# Fall2018AvionicsBay.net
KiCad netlist of a schematic drawn in EAGLE
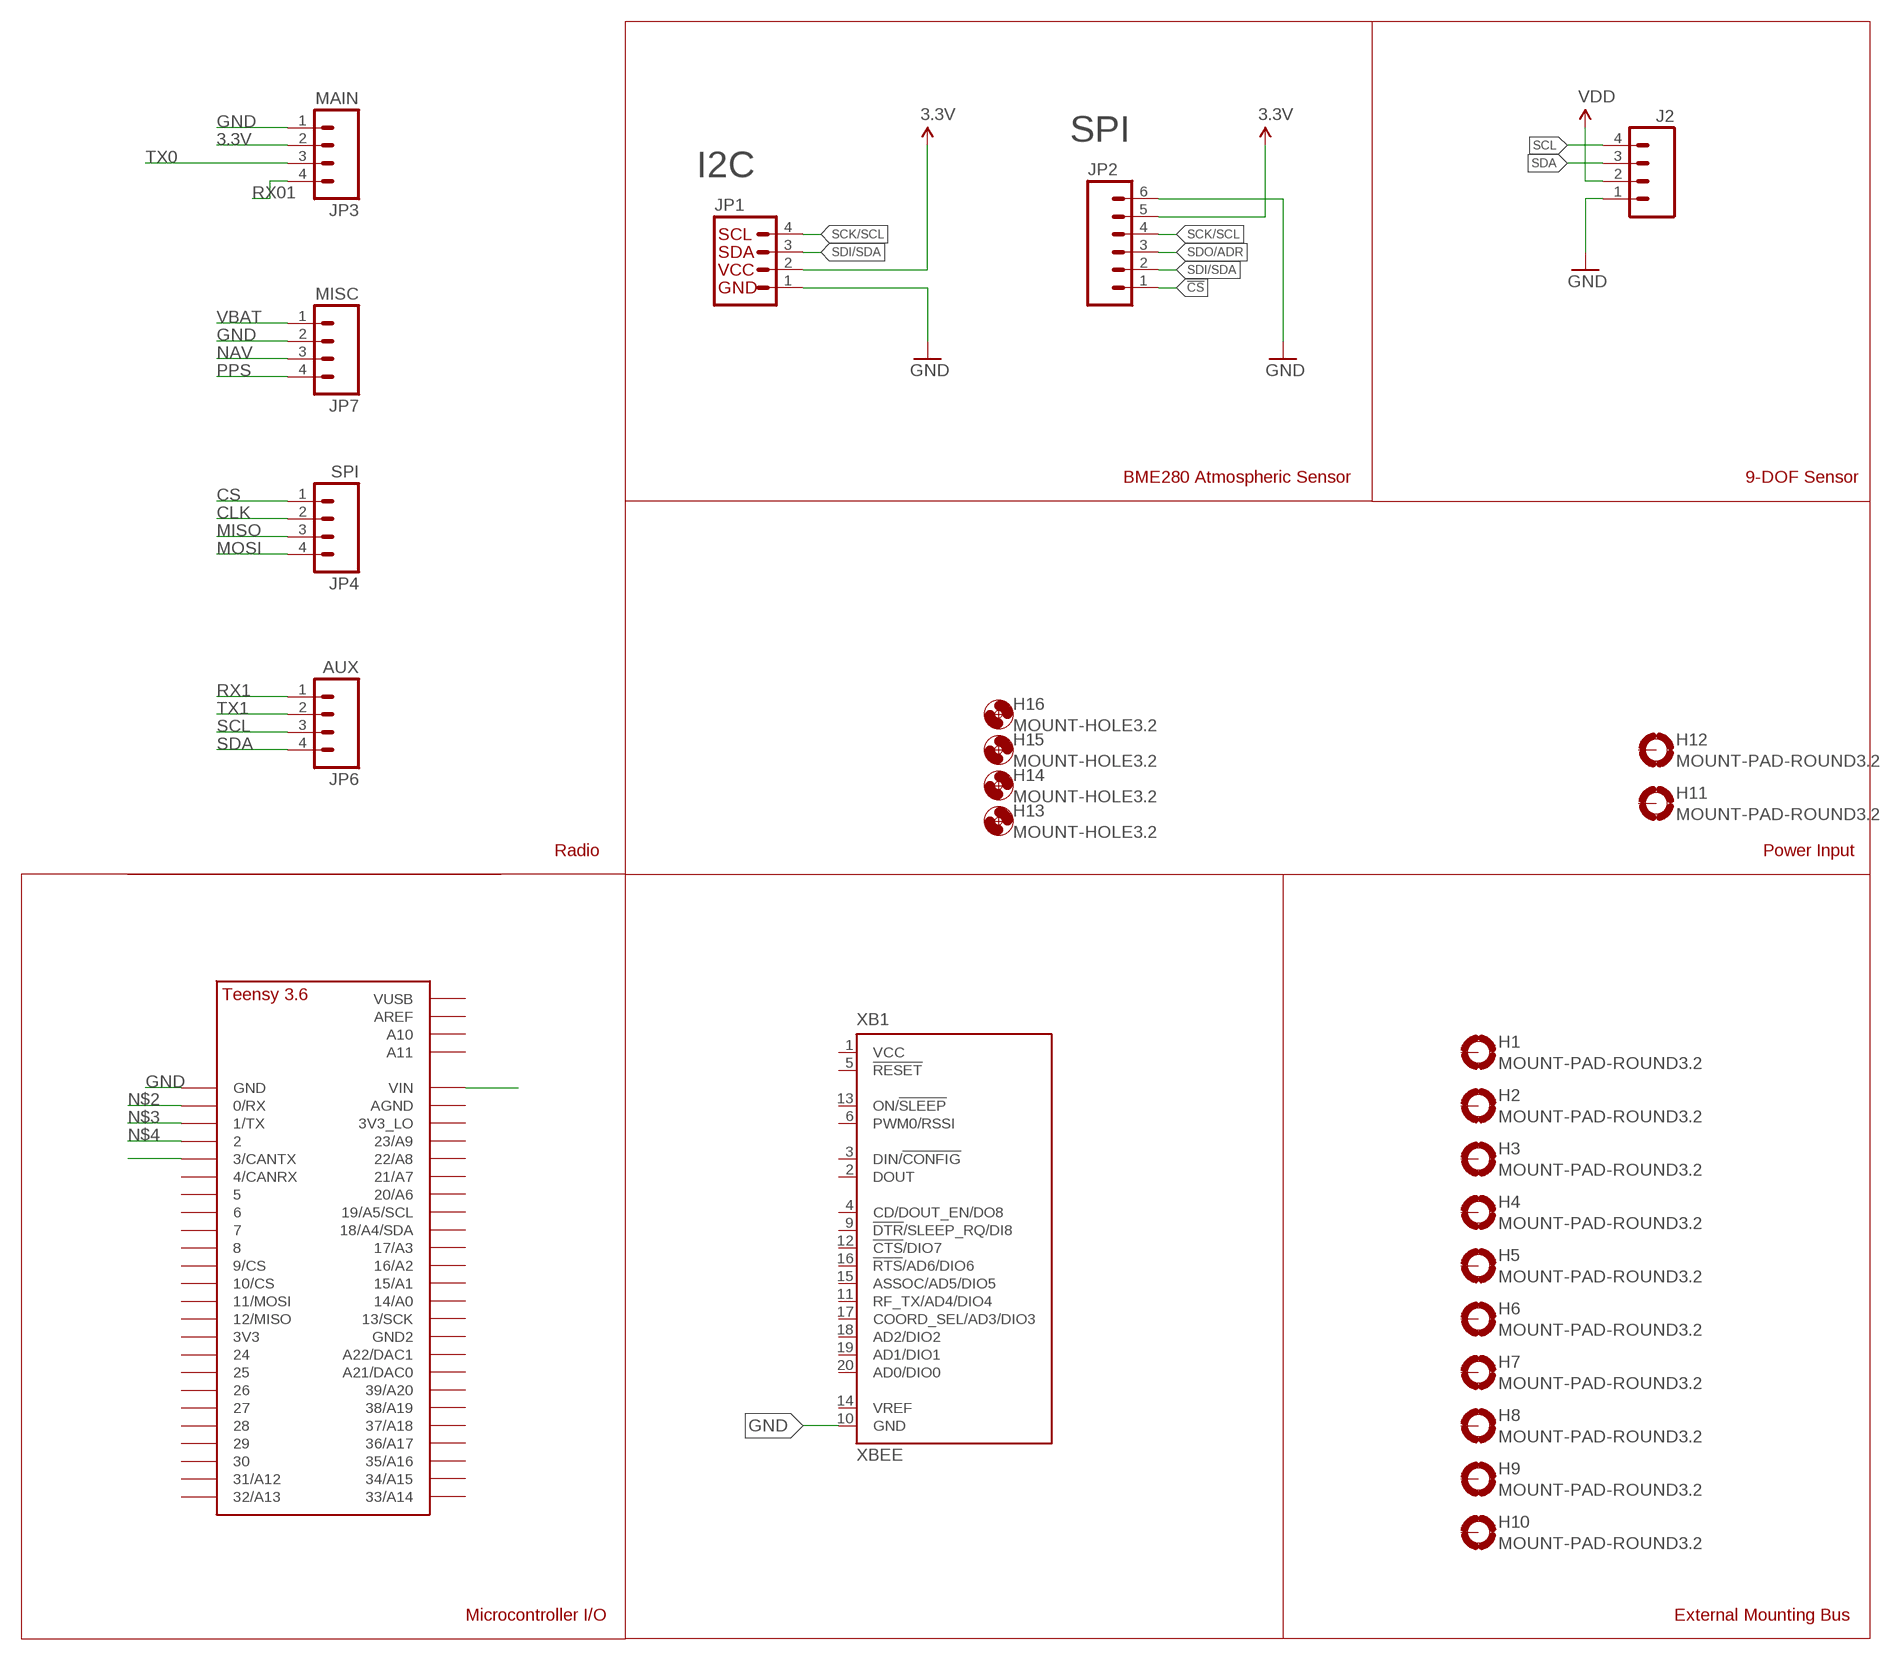
[diagram p0: schematic, sheet 1]

(export (version "E")
  (design (tool "Eeschema 10.0.6"))
  (components
    (comp (ref "H1")
      (value "MOUNT-PAD-ROUND3.2")
      (footprint "eagle-import:3,2-PAD")
      (libsource (lib "eagle-import") (part "MOUNT-PAD-ROUND3.2"))
    )
    (comp (ref "H2")
      (value "MOUNT-PAD-ROUND3.2")
      (footprint "eagle-import:3,2-PAD")
      (libsource (lib "eagle-import") (part "MOUNT-PAD-ROUND3.2"))
    )
    (comp (ref "H3")
      (value "MOUNT-PAD-ROUND3.2")
      (footprint "eagle-import:3,2-PAD")
      (libsource (lib "eagle-import") (part "MOUNT-PAD-ROUND3.2"))
    )
    (comp (ref "H4")
      (value "MOUNT-PAD-ROUND3.2")
      (footprint "eagle-import:3,2-PAD")
      (libsource (lib "eagle-import") (part "MOUNT-PAD-ROUND3.2"))
    )
    (comp (ref "H5")
      (value "MOUNT-PAD-ROUND3.2")
      (footprint "eagle-import:3,2-PAD")
      (libsource (lib "eagle-import") (part "MOUNT-PAD-ROUND3.2"))
    )
    (comp (ref "H6")
      (value "MOUNT-PAD-ROUND3.2")
      (footprint "eagle-import:3,2-PAD")
      (libsource (lib "eagle-import") (part "MOUNT-PAD-ROUND3.2"))
    )
    (comp (ref "H7")
      (value "MOUNT-PAD-ROUND3.2")
      (footprint "eagle-import:3,2-PAD")
      (libsource (lib "eagle-import") (part "MOUNT-PAD-ROUND3.2"))
    )
    (comp (ref "H8")
      (value "MOUNT-PAD-ROUND3.2")
      (footprint "eagle-import:3,2-PAD")
      (libsource (lib "eagle-import") (part "MOUNT-PAD-ROUND3.2"))
    )
    (comp (ref "H9")
      (value "MOUNT-PAD-ROUND3.2")
      (footprint "eagle-import:3,2-PAD")
      (libsource (lib "eagle-import") (part "MOUNT-PAD-ROUND3.2"))
    )
    (comp (ref "H10")
      (value "MOUNT-PAD-ROUND3.2")
      (footprint "eagle-import:3,2-PAD")
      (libsource (lib "eagle-import") (part "MOUNT-PAD-ROUND3.2"))
    )
    (comp (ref "H11")
      (value "MOUNT-PAD-ROUND3.2")
      (footprint "eagle-import:3,2-PAD")
      (libsource (lib "eagle-import") (part "MOUNT-PAD-ROUND3.2"))
    )
    (comp (ref "H12")
      (value "MOUNT-PAD-ROUND3.2")
      (footprint "eagle-import:3,2-PAD")
      (libsource (lib "eagle-import") (part "MOUNT-PAD-ROUND3.2"))
    )
    (comp (ref "H13")
      (value "MOUNT-HOLE3.2")
      (footprint "eagle-import:3,2")
      (libsource (lib "eagle-import") (part "MOUNT-HOLE3.2"))
    )
    (comp (ref "H14")
      (value "MOUNT-HOLE3.2")
      (footprint "eagle-import:3,2")
      (libsource (lib "eagle-import") (part "MOUNT-HOLE3.2"))
    )
    (comp (ref "H15")
      (value "MOUNT-HOLE3.2")
      (footprint "eagle-import:3,2")
      (libsource (lib "eagle-import") (part "MOUNT-HOLE3.2"))
    )
    (comp (ref "H16")
      (value "MOUNT-HOLE3.2")
      (footprint "eagle-import:3,2")
      (libsource (lib "eagle-import") (part "MOUNT-HOLE3.2"))
    )
    (comp (ref "J2")
      (value "M04NO_SILK_ALL_ROUND")
      (footprint "eagle-import:1X04_NO_SILK_ALL_ROUND")
      (libsource (lib "eagle-import") (part "M04NO_SILK_ALL_ROUND"))
    )
    (comp (ref "JP1")
      (value "I2C_STANDARD_NO_SILK")
      (footprint "eagle-import:1X04_NO_SILK")
      (libsource (lib "eagle-import") (part "I2C_STANDARD_NO_SILK"))
    )
    (comp (ref "JP2")
      (value "M06NO_SILK_FEMALE_PTH")
      (footprint "eagle-import:1X06_NO_SILK")
      (libsource (lib "eagle-import") (part "M06NO_SILK_FEMALE_PTH"))
    )
    (comp (ref "JP3")
      (value "MAIN")
      (footprint "eagle-import:1X04")
      (libsource (lib "eagle-import") (part "M04PTH"))
    )
    (comp (ref "JP4")
      (value "SPI")
      (footprint "eagle-import:1X04")
      (libsource (lib "eagle-import") (part "M04PTH"))
    )
    (comp (ref "JP6")
      (value "AUX")
      (footprint "eagle-import:1X04")
      (libsource (lib "eagle-import") (part "M04PTH"))
    )
    (comp (ref "JP7")
      (value "MISC")
      (footprint "eagle-import:1X04")
      (libsource (lib "eagle-import") (part "M04PTH"))
    )
    (comp (ref "U$1")
      (value "TEENSY_3.5/3.6_BASIC")
      (footprint "eagle-import:TEENSY_3.5_3.6_BASIC")
      (libsource (lib "eagle-import") (part "TEENSY_3.5/3.6_BASIC"))
    )
    (comp (ref "XB1")
      (value "XBEE")
      (footprint "eagle-import:XBEE")
      (fields (field (name "MPN") "XBP24-Z7UIT-004"))
      (libsource (lib "eagle-import") (part "XBEE"))
    )
  )
  (nets
    (net (code "1") (name "/CLK") (class "Default")
      (node (ref "JP4") (pin "2") (pinfunction "2_2") (pintype "passive"))
    )
    (net (code "2") (name "/CS") (class "Default")
      (node (ref "JP4") (pin "1") (pinfunction "1_1") (pintype "passive"))
    )
    (net (code "3") (name "/MISO") (class "Default")
      (node (ref "JP4") (pin "3") (pinfunction "3_3") (pintype "passive"))
    )
    (net (code "4") (name "/MOSI") (class "Default")
      (node (ref "JP4") (pin "4") (pinfunction "4_4") (pintype "passive"))
    )
    (net (code "5") (name "/N$2") (class "Default")
      (node (ref "U$1") (pin "0/RX") (pinfunction "0/RX_0/RX") (pintype "bidirectional"))
    )
    (net (code "6") (name "/N$3") (class "Default")
      (node (ref "U$1") (pin "1/TX") (pinfunction "1/TX_1/TX") (pintype "bidirectional"))
    )
    (net (code "7") (name "/N$4") (class "Default")
      (node (ref "U$1") (pin "2") (pinfunction "2_2") (pintype "bidirectional"))
    )
    (net (code "8") (name "/NAV") (class "Default")
      (node (ref "JP7") (pin "3") (pinfunction "3_3") (pintype "passive"))
    )
    (net (code "9") (name "/PPS") (class "Default")
      (node (ref "JP7") (pin "4") (pinfunction "4_4") (pintype "passive"))
    )
    (net (code "10") (name "/RX1") (class "Default")
      (node (ref "JP6") (pin "1") (pinfunction "1_1") (pintype "passive"))
    )
    (net (code "11") (name "/RX01") (class "Default")
      (node (ref "JP3") (pin "4") (pinfunction "4_4") (pintype "passive"))
    )
    (net (code "12") (name "/TX0") (class "Default")
      (node (ref "JP3") (pin "3") (pinfunction "3_3") (pintype "passive"))
    )
    (net (code "13") (name "/TX1") (class "Default")
      (node (ref "JP6") (pin "2") (pinfunction "2_2") (pintype "passive"))
    )
    (net (code "14") (name "/VBAT") (class "Default")
      (node (ref "JP7") (pin "1") (pinfunction "1_1") (pintype "passive"))
    )
    (net (code "15") (name "/VCC") (class "Default")
      (node (ref "XB1") (pin "1") (pinfunction "VCC_1") (pintype "power_in"))
    )
    (net (code "16") (name "/~{CS}") (class "Default")
      (node (ref "JP2") (pin "1") (pinfunction "1_1") (pintype "passive"))
    )
    (net (code "17") (name "3.3V") (class "Default")
      (node (ref "JP1") (pin "2") (pinfunction "2_2") (pintype "passive"))
      (node (ref "JP2") (pin "5") (pinfunction "5_5") (pintype "passive"))
      (node (ref "JP3") (pin "2") (pinfunction "2_2") (pintype "passive"))
    )
    (net (code "18") (name "GND") (class "Default")
      (node (ref "J2") (pin "1") (pinfunction "1_1") (pintype "passive"))
      (node (ref "JP1") (pin "1") (pinfunction "1_1") (pintype "passive"))
      (node (ref "JP2") (pin "6") (pinfunction "6_6") (pintype "passive"))
      (node (ref "JP3") (pin "1") (pinfunction "1_1") (pintype "passive"))
      (node (ref "JP7") (pin "2") (pinfunction "2_2") (pintype "passive"))
      (node (ref "U$1") (pin "GND") (pinfunction "GND_GND") (pintype "bidirectional"))
      (node (ref "XB1") (pin "10") (pinfunction "GND_10") (pintype "power_in"))
    )
    (net (code "19") (name "SCK{slash}SCL") (class "Default")
      (node (ref "JP1") (pin "4") (pinfunction "4_4") (pintype "passive"))
      (node (ref "JP2") (pin "4") (pinfunction "4_4") (pintype "passive"))
    )
    (net (code "20") (name "SCL") (class "Default")
      (node (ref "J2") (pin "4") (pinfunction "4_4") (pintype "passive"))
      (node (ref "JP6") (pin "3") (pinfunction "3_3") (pintype "passive"))
    )
    (net (code "21") (name "SDA") (class "Default")
      (node (ref "J2") (pin "3") (pinfunction "3_3") (pintype "passive"))
      (node (ref "JP6") (pin "4") (pinfunction "4_4") (pintype "passive"))
    )
    (net (code "22") (name "SDI{slash}SDA") (class "Default")
      (node (ref "JP1") (pin "3") (pinfunction "3_3") (pintype "passive"))
      (node (ref "JP2") (pin "2") (pinfunction "2_2") (pintype "passive"))
    )
    (net (code "23") (name "SDO{slash}ADR") (class "Default")
      (node (ref "JP2") (pin "3") (pinfunction "3_3") (pintype "passive"))
    )
    (net (code "24") (name "VDD") (class "Default")
      (node (ref "J2") (pin "2") (pinfunction "2_2") (pintype "passive"))
    )
    (net (code "25") (name "unconnected-(H1-MOUNT-PadB3,2)") (class "Default")
      (node (ref "H1") (pin "B3,2") (pinfunction "MOUNT_B3,2") (pintype "passive"))
    )
    (net (code "26") (name "unconnected-(H2-MOUNT-PadB3,2)") (class "Default")
      (node (ref "H2") (pin "B3,2") (pinfunction "MOUNT_B3,2") (pintype "passive"))
    )
    (net (code "27") (name "unconnected-(H3-MOUNT-PadB3,2)") (class "Default")
      (node (ref "H3") (pin "B3,2") (pinfunction "MOUNT_B3,2") (pintype "passive"))
    )
    (net (code "28") (name "unconnected-(H4-MOUNT-PadB3,2)") (class "Default")
      (node (ref "H4") (pin "B3,2") (pinfunction "MOUNT_B3,2") (pintype "passive"))
    )
    (net (code "29") (name "unconnected-(H5-MOUNT-PadB3,2)") (class "Default")
      (node (ref "H5") (pin "B3,2") (pinfunction "MOUNT_B3,2") (pintype "passive"))
    )
    (net (code "30") (name "unconnected-(H6-MOUNT-PadB3,2)") (class "Default")
      (node (ref "H6") (pin "B3,2") (pinfunction "MOUNT_B3,2") (pintype "passive"))
    )
    (net (code "31") (name "unconnected-(H7-MOUNT-PadB3,2)") (class "Default")
      (node (ref "H7") (pin "B3,2") (pinfunction "MOUNT_B3,2") (pintype "passive"))
    )
    (net (code "32") (name "unconnected-(H8-MOUNT-PadB3,2)") (class "Default")
      (node (ref "H8") (pin "B3,2") (pinfunction "MOUNT_B3,2") (pintype "passive"))
    )
    (net (code "33") (name "unconnected-(H9-MOUNT-PadB3,2)") (class "Default")
      (node (ref "H9") (pin "B3,2") (pinfunction "MOUNT_B3,2") (pintype "passive"))
    )
    (net (code "34") (name "unconnected-(H10-MOUNT-PadB3,2)") (class "Default")
      (node (ref "H10") (pin "B3,2") (pinfunction "MOUNT_B3,2") (pintype "passive"))
    )
    (net (code "35") (name "unconnected-(H11-MOUNT-PadB3,2)") (class "Default")
      (node (ref "H11") (pin "B3,2") (pinfunction "MOUNT_B3,2") (pintype "passive"))
    )
    (net (code "36") (name "unconnected-(H12-MOUNT-PadB3,2)") (class "Default")
      (node (ref "H12") (pin "B3,2") (pinfunction "MOUNT_B3,2") (pintype "passive"))
    )
    (net (code "37") (name "unconnected-(U$1-A21{slash}DAC0-Pad21{slash}DAC0)") (class "Default")
      (node (ref "U$1") (pin "21/DAC0") (pinfunction "A21/DAC0_21/DAC0") (pintype "bidirectional"))
    )
    (net (code "38") (name "unconnected-(U$1-Pad3V3)") (class "Default")
      (node (ref "U$1") (pin "3V3") (pinfunction "3V3_3V3") (pintype "bidirectional"))
    )
    (net (code "39") (name "unconnected-(U$1-Pad3V3_LO)") (class "Default")
      (node (ref "U$1") (pin "3V3_LO") (pinfunction "3V3_LO_3V3_LO") (pintype "bidirectional"))
    )
    (net (code "40") (name "unconnected-(U$1-Pad3{slash}CANTX)") (class "Default")
      (node (ref "U$1") (pin "3/CANTX") (pinfunction "3/CANTX_3/CANTX") (pintype "bidirectional"))
    )
    (net (code "41") (name "unconnected-(U$1-Pad4{slash}CANRX)") (class "Default")
      (node (ref "U$1") (pin "4/CANRX") (pinfunction "4/CANRX_4/CANRX") (pintype "bidirectional"))
    )
    (net (code "42") (name "unconnected-(U$1-Pad5)") (class "Default")
      (node (ref "U$1") (pin "5") (pinfunction "5_5") (pintype "bidirectional"))
    )
    (net (code "43") (name "unconnected-(U$1-Pad6)") (class "Default")
      (node (ref "U$1") (pin "6") (pinfunction "6_6") (pintype "bidirectional"))
    )
    (net (code "44") (name "unconnected-(U$1-Pad7)") (class "Default")
      (node (ref "U$1") (pin "7") (pinfunction "7_7") (pintype "bidirectional"))
    )
    (net (code "45") (name "unconnected-(U$1-Pad8)") (class "Default")
      (node (ref "U$1") (pin "8") (pinfunction "8_8") (pintype "bidirectional"))
    )
    (net (code "46") (name "unconnected-(U$1-Pad9{slash}CS)") (class "Default")
      (node (ref "U$1") (pin "9/CS") (pinfunction "9/CS_9/CS") (pintype "bidirectional"))
    )
    (net (code "47") (name "unconnected-(U$1-Pad10{slash}CS)") (class "Default")
      (node (ref "U$1") (pin "10/CS") (pinfunction "10/CS_10/CS") (pintype "bidirectional"))
    )
    (net (code "48") (name "unconnected-(U$1-Pad11{slash}MOSI)") (class "Default")
      (node (ref "U$1") (pin "11/MOSI") (pinfunction "11/MOSI_11/MOSI") (pintype "bidirectional"))
    )
    (net (code "49") (name "unconnected-(U$1-Pad12{slash}MISO)") (class "Default")
      (node (ref "U$1") (pin "12/MISO") (pinfunction "12/MISO_12/MISO") (pintype "bidirectional"))
    )
    (net (code "50") (name "unconnected-(U$1-Pad13{slash}SCK)") (class "Default")
      (node (ref "U$1") (pin "13/SCK") (pinfunction "13/SCK_13/SCK") (pintype "bidirectional"))
    )
    (net (code "51") (name "unconnected-(U$1-Pad14{slash}A0)") (class "Default")
      (node (ref "U$1") (pin "14/A0") (pinfunction "14/A0_14/A0") (pintype "bidirectional"))
    )
    (net (code "52") (name "unconnected-(U$1-Pad15{slash}A1)") (class "Default")
      (node (ref "U$1") (pin "15/A1") (pinfunction "15/A1_15/A1") (pintype "bidirectional"))
    )
    (net (code "53") (name "unconnected-(U$1-Pad16{slash}A2)") (class "Default")
      (node (ref "U$1") (pin "16/A2") (pinfunction "16/A2_16/A2") (pintype "bidirectional"))
    )
    (net (code "54") (name "unconnected-(U$1-Pad17{slash}A3)") (class "Default")
      (node (ref "U$1") (pin "17/A3") (pinfunction "17/A3_17/A3") (pintype "bidirectional"))
    )
    (net (code "55") (name "unconnected-(U$1-Pad18{slash}A4{slash}SDA)") (class "Default")
      (node (ref "U$1") (pin "18/A4/SDA") (pinfunction "18/A4/SDA_18/A4/SDA") (pintype "bidirectional"))
    )
    (net (code "56") (name "unconnected-(U$1-Pad19{slash}A5{slash}SCL)") (class "Default")
      (node (ref "U$1") (pin "19/A5/SCL") (pinfunction "19/A5/SCL_19/A5/SCL") (pintype "bidirectional"))
    )
    (net (code "57") (name "unconnected-(U$1-Pad20{slash}A6)") (class "Default")
      (node (ref "U$1") (pin "20/A6") (pinfunction "20/A6_20/A6") (pintype "bidirectional"))
    )
    (net (code "58") (name "unconnected-(U$1-Pad21{slash}A7)") (class "Default")
      (node (ref "U$1") (pin "21/A7") (pinfunction "21/A7_21/A7") (pintype "bidirectional"))
    )
    (net (code "59") (name "unconnected-(U$1-Pad22{slash}A8)") (class "Default")
      (node (ref "U$1") (pin "22/A8") (pinfunction "22/A8_22/A8") (pintype "bidirectional"))
    )
    (net (code "60") (name "unconnected-(U$1-Pad23{slash}A9)") (class "Default")
      (node (ref "U$1") (pin "23/A9") (pinfunction "23/A9_23/A9") (pintype "bidirectional"))
    )
    (net (code "61") (name "unconnected-(U$1-Pad24)") (class "Default")
      (node (ref "U$1") (pin "24") (pinfunction "24_24") (pintype "bidirectional"))
    )
    (net (code "62") (name "unconnected-(U$1-Pad25)") (class "Default")
      (node (ref "U$1") (pin "25") (pinfunction "25_25") (pintype "bidirectional"))
    )
    (net (code "63") (name "unconnected-(U$1-Pad26)") (class "Default")
      (node (ref "U$1") (pin "26") (pinfunction "26_26") (pintype "bidirectional"))
    )
    (net (code "64") (name "unconnected-(U$1-Pad27)") (class "Default")
      (node (ref "U$1") (pin "27") (pinfunction "27_27") (pintype "bidirectional"))
    )
    (net (code "65") (name "unconnected-(U$1-Pad28)") (class "Default")
      (node (ref "U$1") (pin "28") (pinfunction "28_28") (pintype "bidirectional"))
    )
    (net (code "66") (name "unconnected-(U$1-Pad29)") (class "Default")
      (node (ref "U$1") (pin "29") (pinfunction "29_29") (pintype "bidirectional"))
    )
    (net (code "67") (name "unconnected-(U$1-Pad30)") (class "Default")
      (node (ref "U$1") (pin "30") (pinfunction "30_30") (pintype "bidirectional"))
    )
    (net (code "68") (name "unconnected-(U$1-Pad31{slash}A12)") (class "Default")
      (node (ref "U$1") (pin "31/A12") (pinfunction "31/A12_31/A12") (pintype "bidirectional"))
    )
    (net (code "69") (name "unconnected-(U$1-Pad32{slash}A13)") (class "Default")
      (node (ref "U$1") (pin "32/A13") (pinfunction "32/A13_32/A13") (pintype "bidirectional"))
    )
    (net (code "70") (name "unconnected-(U$1-Pad33{slash}A14)") (class "Default")
      (node (ref "U$1") (pin "33/A14") (pinfunction "33/A14_33/A14") (pintype "bidirectional"))
    )
    (net (code "71") (name "unconnected-(U$1-Pad34{slash}A15)") (class "Default")
      (node (ref "U$1") (pin "34/A15") (pinfunction "34/A15_34/A15") (pintype "bidirectional"))
    )
    (net (code "72") (name "unconnected-(U$1-Pad35{slash}A16)") (class "Default")
      (node (ref "U$1") (pin "35/A16") (pinfunction "35/A16_35/A16") (pintype "bidirectional"))
    )
    (net (code "73") (name "unconnected-(U$1-Pad36{slash}A17)") (class "Default")
      (node (ref "U$1") (pin "36/A17") (pinfunction "36/A17_36/A17") (pintype "bidirectional"))
    )
    (net (code "74") (name "unconnected-(U$1-Pad37{slash}A18)") (class "Default")
      (node (ref "U$1") (pin "37/A18") (pinfunction "37/A18_37/A18") (pintype "bidirectional"))
    )
    (net (code "75") (name "unconnected-(U$1-Pad38{slash}A19)") (class "Default")
      (node (ref "U$1") (pin "38/A19") (pinfunction "38/A19_38/A19") (pintype "bidirectional"))
    )
    (net (code "76") (name "unconnected-(U$1-Pad39{slash}A20)") (class "Default")
      (node (ref "U$1") (pin "39/A20") (pinfunction "39/A20_39/A20") (pintype "bidirectional"))
    )
    (net (code "77") (name "unconnected-(U$1-PadA10)") (class "Default")
      (node (ref "U$1") (pin "A10") (pinfunction "A10_A10") (pintype "bidirectional"))
    )
    (net (code "78") (name "unconnected-(U$1-PadA11)") (class "Default")
      (node (ref "U$1") (pin "A11") (pinfunction "A11_A11") (pintype "bidirectional"))
    )
    (net (code "79") (name "unconnected-(U$1-PadA22{slash}DAC1)") (class "Default")
      (node (ref "U$1") (pin "A22/DAC1") (pinfunction "A22/DAC1_A22/DAC1") (pintype "bidirectional"))
    )
    (net (code "80") (name "unconnected-(U$1-PadAGND)") (class "Default")
      (node (ref "U$1") (pin "AGND") (pinfunction "AGND_AGND") (pintype "bidirectional"))
    )
    (net (code "81") (name "unconnected-(U$1-PadAREF)") (class "Default")
      (node (ref "U$1") (pin "AREF") (pinfunction "AREF_AREF") (pintype "bidirectional"))
    )
    (net (code "82") (name "unconnected-(U$1-PadGND2)") (class "Default")
      (node (ref "U$1") (pin "GND2") (pinfunction "GND2_GND2") (pintype "bidirectional"))
    )
    (net (code "83") (name "unconnected-(U$1-PadVIN)") (class "Default")
      (node (ref "U$1") (pin "VIN") (pinfunction "VIN_VIN") (pintype "bidirectional"))
    )
    (net (code "84") (name "unconnected-(U$1-PadVUSB)") (class "Default")
      (node (ref "U$1") (pin "VUSB") (pinfunction "VUSB_VUSB") (pintype "bidirectional"))
    )
    (net (code "85") (name "unconnected-(XB1-AD0{slash}DIO0-Pad20)") (class "Default")
      (node (ref "XB1") (pin "20") (pinfunction "AD0/DIO0_20") (pintype "bidirectional"))
    )
    (net (code "86") (name "unconnected-(XB1-AD1{slash}DIO1-Pad19)") (class "Default")
      (node (ref "XB1") (pin "19") (pinfunction "AD1/DIO1_19") (pintype "bidirectional"))
    )
    (net (code "87") (name "unconnected-(XB1-AD2{slash}DIO2-Pad18)") (class "Default")
      (node (ref "XB1") (pin "18") (pinfunction "AD2/DIO2_18") (pintype "bidirectional"))
    )
    (net (code "88") (name "unconnected-(XB1-ASSOC{slash}AD5{slash}DIO5-Pad15)") (class "Default")
      (node (ref "XB1") (pin "15") (pinfunction "ASSOC/AD5/DIO5_15") (pintype "bidirectional"))
    )
    (net (code "89") (name "unconnected-(XB1-CD{slash}DOUT_EN{slash}DO8-Pad4)") (class "Default")
      (node (ref "XB1") (pin "4") (pinfunction "CD/DOUT_EN/DO8_4") (pintype "output"))
    )
    (net (code "90") (name "unconnected-(XB1-COORD_SEL{slash}AD3{slash}DIO3-Pad17)") (class "Default")
      (node (ref "XB1") (pin "17") (pinfunction "COORD_SEL/AD3/DIO3_17") (pintype "bidirectional"))
    )
    (net (code "91") (name "unconnected-(XB1-DIN{slash}~{CONFIG}-Pad3)") (class "Default")
      (node (ref "XB1") (pin "3") (pinfunction "DIN/~{CONFIG}_3") (pintype "input"))
    )
    (net (code "92") (name "unconnected-(XB1-DOUT-Pad2)") (class "Default")
      (node (ref "XB1") (pin "2") (pinfunction "DOUT_2") (pintype "output"))
    )
    (net (code "93") (name "unconnected-(XB1-ON{slash}~{SLEEP}-Pad13)") (class "Default")
      (node (ref "XB1") (pin "13") (pinfunction "ON/~{SLEEP}_13") (pintype "output"))
    )
    (net (code "94") (name "unconnected-(XB1-PWM0{slash}RSSI-Pad6)") (class "Default")
      (node (ref "XB1") (pin "6") (pinfunction "PWM0/RSSI_6") (pintype "output"))
    )
    (net (code "95") (name "unconnected-(XB1-RF_TX{slash}AD4{slash}DIO4-Pad11)") (class "Default")
      (node (ref "XB1") (pin "11") (pinfunction "RF_TX/AD4/DIO4_11") (pintype "bidirectional"))
    )
    (net (code "96") (name "unconnected-(XB1-VREF-Pad14)") (class "Default")
      (node (ref "XB1") (pin "14") (pinfunction "VREF_14") (pintype "input"))
    )
    (net (code "97") (name "unconnected-(XB1-~{CTS}{slash}DIO7-Pad12)") (class "Default")
      (node (ref "XB1") (pin "12") (pinfunction "~{CTS}/DIO7_12") (pintype "bidirectional"))
    )
    (net (code "98") (name "unconnected-(XB1-~{DTR}{slash}SLEEP_RQ{slash}DI8-Pad9)") (class "Default")
      (node (ref "XB1") (pin "9") (pinfunction "~{DTR}/SLEEP_RQ/DI8_9") (pintype "bidirectional"))
    )
    (net (code "99") (name "unconnected-(XB1-~{RESET}-Pad5)") (class "Default")
      (node (ref "XB1") (pin "5") (pinfunction "~{RESET}_5") (pintype "input"))
    )
    (net (code "100") (name "unconnected-(XB1-~{RTS}{slash}AD6{slash}DIO6-Pad16)") (class "Default")
      (node (ref "XB1") (pin "16") (pinfunction "~{RTS}/AD6/DIO6_16") (pintype "bidirectional"))
    )
  )
)
